# HW_Mechanical_Parts.net
KiCad netlist of a schematic drawn in Altium Designer
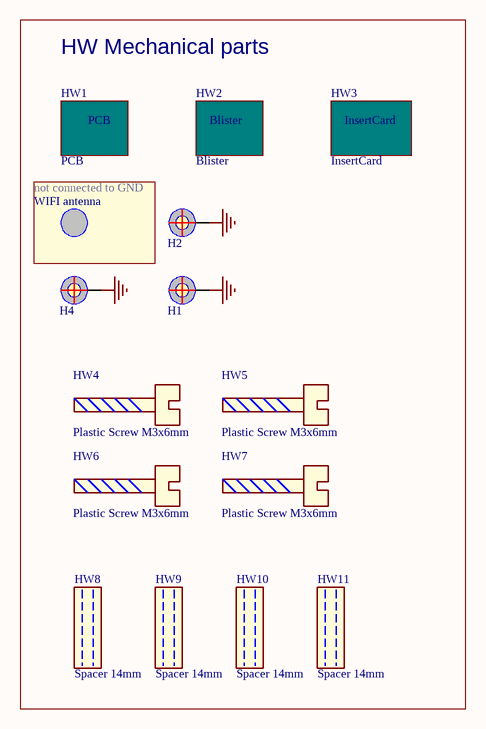
[diagram p0: HW_Mechanical_Parts.SchDoc]

(export (version "E")
  (design (tool "Eeschema 10.0.6"))
  (components
    (comp (ref "H1")
      (value "POSITION HOLE C6D3R5")
      (footprint "HOLE_C6D3R5")
      (libsource (lib "MCD_TOOLS_MISCELLANEOUS") (part "POSITION HOLE C6D3R5"))
    )
    (comp (ref "H2")
      (value "POSITION HOLE C6D3R5")
      (footprint "HOLE_C6D3R5")
      (libsource (lib "MCD_TOOLS_MISCELLANEOUS") (part "POSITION HOLE C6D3R5"))
    )
    (comp (ref "H4")
      (value "POSITION HOLE C6D3R5")
      (footprint "HOLE_C6D3R5")
      (libsource (lib "MCD_TOOLS_MISCELLANEOUS") (part "POSITION HOLE C6D3R5"))
    )
    (comp (ref "HW1") (value "PCB") (libsource (lib "MCD_TEMP_NPA") (part "PCB")))
    (comp (ref "HW2") (value "Blister") (libsource (lib "MCD_TEMP_NPA") (part "Blister")))
    (comp (ref "HW3") (value "InsertCard") (libsource (lib "MCD_TEMP_NPA") (part "InsertCard")))
    (comp (ref "HW4")
      (value "Plastic Screw M3x6mm")
      (description "Plastic screw")
      (libsource (lib "MCD_TEMP_PCH") (part "Plastic Screw M3x6mm"))
    )
    (comp (ref "HW5")
      (value "Plastic Screw M3x6mm")
      (description "Plastic screw")
      (libsource (lib "MCD_TEMP_PCH") (part "Plastic Screw M3x6mm"))
    )
    (comp (ref "HW6")
      (value "Plastic Screw M3x6mm")
      (description "Plastic screw")
      (libsource (lib "MCD_TEMP_PCH") (part "Plastic Screw M3x6mm"))
    )
    (comp (ref "HW7")
      (value "Plastic Screw M3x6mm")
      (description "Plastic screw")
      (libsource (lib "MCD_TEMP_PCH") (part "Plastic Screw M3x6mm"))
    )
    (comp (ref "HW8")
      (value "Spacer 14mm")
      (description "Plastic spacer")
      (libsource (lib "MCD_TEMP_PCH") (part "Plastic Spacer D4.5x14, M3x0.5"))
    )
    (comp (ref "HW9")
      (value "Spacer 14mm")
      (description "Plastic spacer")
      (libsource (lib "MCD_TEMP_PCH") (part "Plastic Spacer D4.5x14, M3x0.5"))
    )
    (comp (ref "HW10")
      (value "Spacer 14mm")
      (description "Plastic spacer")
      (libsource (lib "MCD_TEMP_PCH") (part "Plastic Spacer D4.5x14, M3x0.5"))
    )
    (comp (ref "HW11")
      (value "Spacer 14mm")
      (description "Plastic spacer")
      (libsource (lib "MCD_TEMP_PCH") (part "Plastic Spacer D4.5x14, M3x0.5"))
    )
  )
  (nets
    (net (code "1") (name "GND") (class "Default")
      (node (ref "H1") (pin "1") (pinfunction "1_1") (pintype "passive"))
      (node (ref "H2") (pin "1") (pinfunction "1_1") (pintype "passive"))
      (node (ref "H4") (pin "1") (pinfunction "1_1") (pintype "passive"))
    )
  )
)
